# demo7.net
KiCad netlist of a schematic drawn in EAGLE
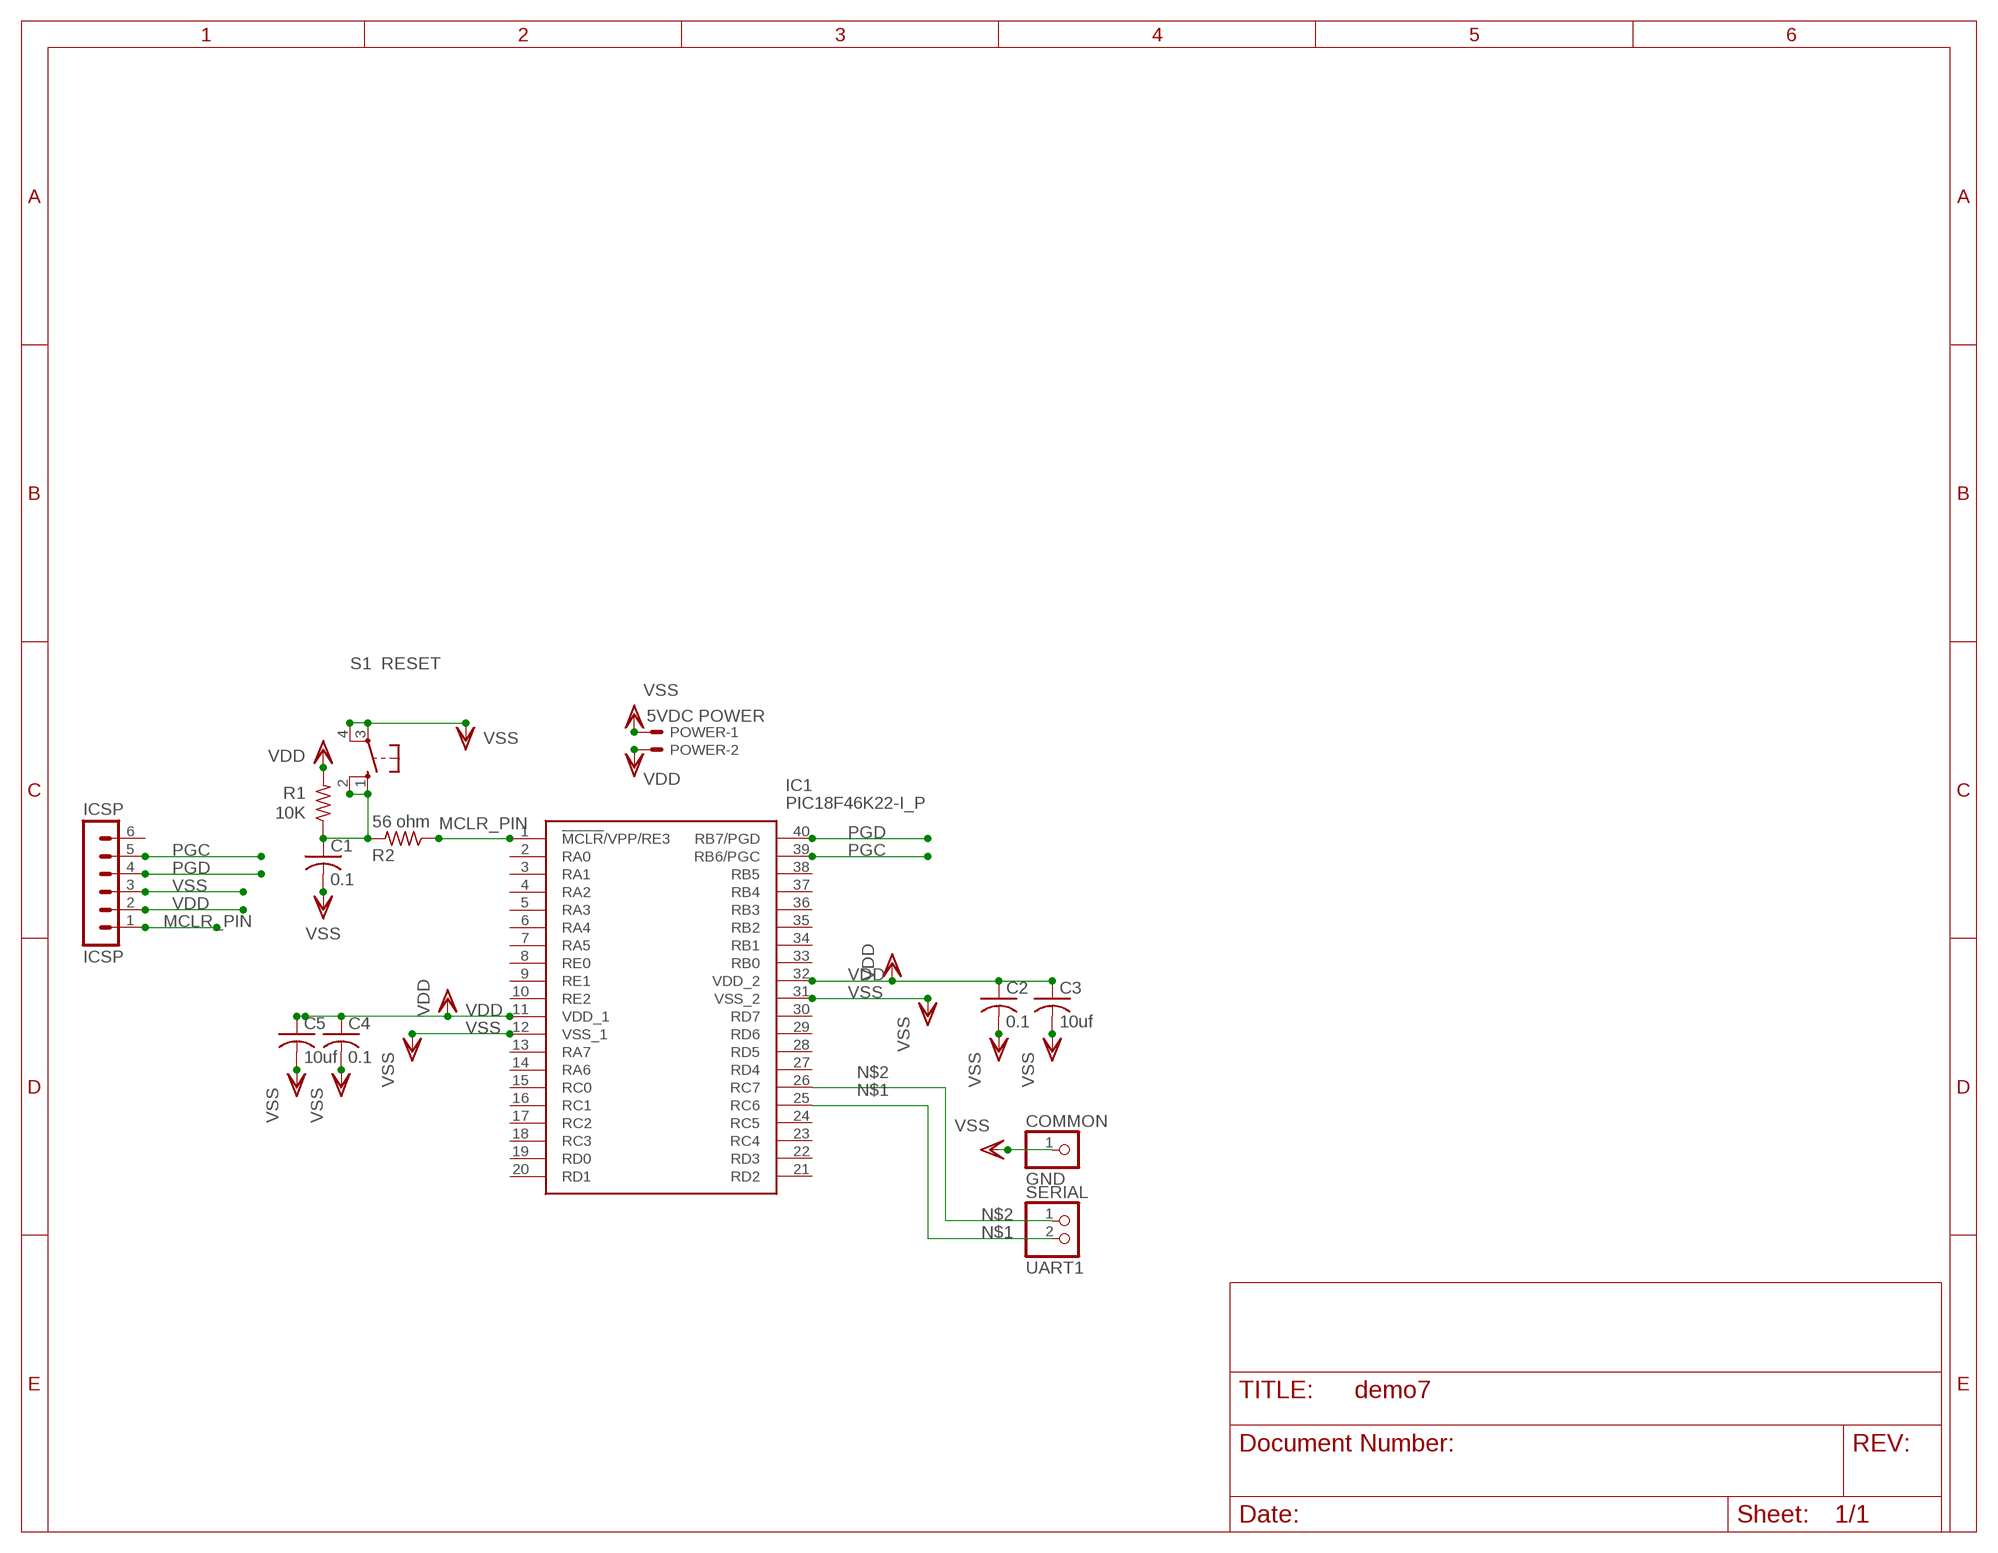
[diagram p0: schematic, sheet 1]

(export (version "E")
  (design (tool "Eeschema 10.0.6"))
  (components
    (comp (ref "C1")
      (value "0.1")
      (footprint "eagle-import:C025-030X050")
      (libsource (lib "eagle-import") (part "C-US025-030X050"))
    )
    (comp (ref "C2")
      (value "0.1")
      (footprint "eagle-import:C025-030X050")
      (libsource (lib "eagle-import") (part "C-US025-030X050"))
    )
    (comp (ref "C3")
      (value "10uf")
      (footprint "eagle-import:C025-030X050")
      (libsource (lib "eagle-import") (part "C-US025-030X050"))
    )
    (comp (ref "C4")
      (value "0.1")
      (footprint "eagle-import:C025-030X050")
      (libsource (lib "eagle-import") (part "C-US025-030X050"))
    )
    (comp (ref "C5")
      (value "10uf")
      (footprint "eagle-import:C025-030X050")
      (libsource (lib "eagle-import") (part "C-US025-030X050"))
    )
    (comp (ref "COMMON")
      (value "GND")
      (footprint "eagle-import:1X01")
      (libsource (lib "eagle-import") (part "PINHD-1X1"))
    )
    (comp (ref "IC1")
      (value "PIC18F46K22-I_P")
      (footprint "eagle-import:DIP1543W58P254L5175H635Q40N")
      (fields
        (field (name "MANUFACTURER_PART_NUMBER") "PIC18F46K22-I/P")
        (field (name "MOUSER_PART_NUMBER") "579-PIC18F46K22IP")
      )
      (libsource (lib "eagle-import") (part "PIC18F46K22-I_P"))
    )
    (comp (ref "ICSP")
      (value "ICSP")
      (footprint "eagle-import:MA06-1")
      (libsource (lib "eagle-import") (part "MA06-1"))
    )
    (comp (ref "POWER")
      (value "5VDC POWER")
      (footprint "eagle-import:22-23-2021")
      (fields (field (name "MF") "MOLEX") (field (name "MPN") "22-23-2021"))
      (libsource (lib "eagle-import") (part "22-23-2021"))
    )
    (comp (ref "R1")
      (value "10K")
      (footprint "eagle-import:0204_7")
      (libsource (lib "eagle-import") (part "R-US_0204/7"))
    )
    (comp (ref "R2")
      (value "56 ohm")
      (footprint "eagle-import:0204_7")
      (libsource (lib "eagle-import") (part "R-US_0204/7"))
    )
    (comp (ref "S1")
      (value "RESET")
      (footprint "eagle-import:B3F-10XX")
      (fields (field (name "MPN") "B3F-1000"))
      (libsource (lib "eagle-import") (part "10-XX"))
    )
    (comp (ref "SERIAL")
      (value "UART1")
      (footprint "eagle-import:1X02")
      (libsource (lib "eagle-import") (part "PINHD-1X2"))
    )
  )
  (nets
    (net (code "1") (name "/MCLR_PIN") (class "Default")
      (node (ref "IC1") (pin "1") (pinfunction "~{MCLR}/VPP/RE3_1") (pintype "bidirectional"))
      (node (ref "ICSP") (pin "1") (pinfunction "1_1") (pintype "passive"))
      (node (ref "R2") (pin "1") (pinfunction "1_1") (pintype "passive"))
    )
    (net (code "2") (name "/N$1") (class "Default")
      (node (ref "IC1") (pin "25") (pinfunction "RC6_25") (pintype "bidirectional"))
      (node (ref "SERIAL") (pin "2") (pinfunction "2_2") (pintype "passive"))
    )
    (net (code "3") (name "/N$2") (class "Default")
      (node (ref "IC1") (pin "26") (pinfunction "RC7_26") (pintype "bidirectional"))
      (node (ref "SERIAL") (pin "1") (pinfunction "1_1") (pintype "passive"))
    )
    (net (code "4") (name "/PGC") (class "Default")
      (node (ref "IC1") (pin "39") (pinfunction "RB6/PGC_39") (pintype "bidirectional"))
      (node (ref "ICSP") (pin "5") (pinfunction "5_5") (pintype "passive"))
    )
    (net (code "5") (name "/PGD") (class "Default")
      (node (ref "IC1") (pin "40") (pinfunction "RB7/PGD_40") (pintype "bidirectional"))
      (node (ref "ICSP") (pin "4") (pinfunction "4_4") (pintype "passive"))
    )
    (net (code "6") (name "Net-(S1-S)") (class "Default")
      (node (ref "C1") (pin "1") (pinfunction "1_1") (pintype "passive"))
      (node (ref "R1") (pin "1") (pinfunction "1_1") (pintype "passive"))
      (node (ref "R2") (pin "2") (pinfunction "2_2") (pintype "passive"))
      (node (ref "S1") (pin "1") (pinfunction "S_1") (pintype "passive"))
      (node (ref "S1") (pin "2") (pinfunction "S1_2") (pintype "passive"))
    )
    (net (code "7") (name "VDD") (class "Default")
      (node (ref "C2") (pin "1") (pinfunction "1_1") (pintype "passive"))
      (node (ref "C3") (pin "1") (pinfunction "1_1") (pintype "passive"))
      (node (ref "C4") (pin "1") (pinfunction "1_1") (pintype "passive"))
      (node (ref "C5") (pin "1") (pinfunction "1_1") (pintype "passive"))
      (node (ref "IC1") (pin "11") (pinfunction "VDD_1_11") (pintype "bidirectional"))
      (node (ref "IC1") (pin "32") (pinfunction "VDD_2_32") (pintype "bidirectional"))
      (node (ref "ICSP") (pin "2") (pinfunction "2_2") (pintype "passive"))
      (node (ref "POWER") (pin "2") (pinfunction "S_2") (pintype "passive"))
      (node (ref "R1") (pin "2") (pinfunction "2_2") (pintype "passive"))
    )
    (net (code "8") (name "VSS") (class "Default")
      (node (ref "C1") (pin "2") (pinfunction "2_2") (pintype "passive"))
      (node (ref "C2") (pin "2") (pinfunction "2_2") (pintype "passive"))
      (node (ref "C3") (pin "2") (pinfunction "2_2") (pintype "passive"))
      (node (ref "C4") (pin "2") (pinfunction "2_2") (pintype "passive"))
      (node (ref "C5") (pin "2") (pinfunction "2_2") (pintype "passive"))
      (node (ref "COMMON") (pin "1") (pinfunction "1_1") (pintype "passive"))
      (node (ref "IC1") (pin "12") (pinfunction "VSS_1_12") (pintype "bidirectional"))
      (node (ref "IC1") (pin "31") (pinfunction "VSS_2_31") (pintype "bidirectional"))
      (node (ref "ICSP") (pin "3") (pinfunction "3_3") (pintype "passive"))
      (node (ref "POWER") (pin "1") (pinfunction "S_1") (pintype "passive"))
      (node (ref "S1") (pin "3") (pinfunction "P_3") (pintype "passive"))
      (node (ref "S1") (pin "4") (pinfunction "P1_4") (pintype "passive"))
    )
    (net (code "9") (name "unconnected-(IC1-RA0-Pad2)") (class "Default")
      (node (ref "IC1") (pin "2") (pinfunction "RA0_2") (pintype "bidirectional"))
    )
    (net (code "10") (name "unconnected-(IC1-RA1-Pad3)") (class "Default")
      (node (ref "IC1") (pin "3") (pinfunction "RA1_3") (pintype "bidirectional"))
    )
    (net (code "11") (name "unconnected-(IC1-RA2-Pad4)") (class "Default")
      (node (ref "IC1") (pin "4") (pinfunction "RA2_4") (pintype "bidirectional"))
    )
    (net (code "12") (name "unconnected-(IC1-RA3-Pad5)") (class "Default")
      (node (ref "IC1") (pin "5") (pinfunction "RA3_5") (pintype "bidirectional"))
    )
    (net (code "13") (name "unconnected-(IC1-RA4-Pad6)") (class "Default")
      (node (ref "IC1") (pin "6") (pinfunction "RA4_6") (pintype "bidirectional"))
    )
    (net (code "14") (name "unconnected-(IC1-RA5-Pad7)") (class "Default")
      (node (ref "IC1") (pin "7") (pinfunction "RA5_7") (pintype "bidirectional"))
    )
    (net (code "15") (name "unconnected-(IC1-RA6-Pad14)") (class "Default")
      (node (ref "IC1") (pin "14") (pinfunction "RA6_14") (pintype "bidirectional"))
    )
    (net (code "16") (name "unconnected-(IC1-RA7-Pad13)") (class "Default")
      (node (ref "IC1") (pin "13") (pinfunction "RA7_13") (pintype "bidirectional"))
    )
    (net (code "17") (name "unconnected-(IC1-RB0-Pad33)") (class "Default")
      (node (ref "IC1") (pin "33") (pinfunction "RB0_33") (pintype "bidirectional"))
    )
    (net (code "18") (name "unconnected-(IC1-RB1-Pad34)") (class "Default")
      (node (ref "IC1") (pin "34") (pinfunction "RB1_34") (pintype "bidirectional"))
    )
    (net (code "19") (name "unconnected-(IC1-RB2-Pad35)") (class "Default")
      (node (ref "IC1") (pin "35") (pinfunction "RB2_35") (pintype "bidirectional"))
    )
    (net (code "20") (name "unconnected-(IC1-RB3-Pad36)") (class "Default")
      (node (ref "IC1") (pin "36") (pinfunction "RB3_36") (pintype "bidirectional"))
    )
    (net (code "21") (name "unconnected-(IC1-RB4-Pad37)") (class "Default")
      (node (ref "IC1") (pin "37") (pinfunction "RB4_37") (pintype "bidirectional"))
    )
    (net (code "22") (name "unconnected-(IC1-RB5-Pad38)") (class "Default")
      (node (ref "IC1") (pin "38") (pinfunction "RB5_38") (pintype "bidirectional"))
    )
    (net (code "23") (name "unconnected-(IC1-RC0-Pad15)") (class "Default")
      (node (ref "IC1") (pin "15") (pinfunction "RC0_15") (pintype "bidirectional"))
    )
    (net (code "24") (name "unconnected-(IC1-RC1-Pad16)") (class "Default")
      (node (ref "IC1") (pin "16") (pinfunction "RC1_16") (pintype "bidirectional"))
    )
    (net (code "25") (name "unconnected-(IC1-RC2-Pad17)") (class "Default")
      (node (ref "IC1") (pin "17") (pinfunction "RC2_17") (pintype "bidirectional"))
    )
    (net (code "26") (name "unconnected-(IC1-RC3-Pad18)") (class "Default")
      (node (ref "IC1") (pin "18") (pinfunction "RC3_18") (pintype "bidirectional"))
    )
    (net (code "27") (name "unconnected-(IC1-RC4-Pad23)") (class "Default")
      (node (ref "IC1") (pin "23") (pinfunction "RC4_23") (pintype "bidirectional"))
    )
    (net (code "28") (name "unconnected-(IC1-RC5-Pad24)") (class "Default")
      (node (ref "IC1") (pin "24") (pinfunction "RC5_24") (pintype "bidirectional"))
    )
    (net (code "29") (name "unconnected-(IC1-RD0-Pad19)") (class "Default")
      (node (ref "IC1") (pin "19") (pinfunction "RD0_19") (pintype "bidirectional"))
    )
    (net (code "30") (name "unconnected-(IC1-RD1-Pad20)") (class "Default")
      (node (ref "IC1") (pin "20") (pinfunction "RD1_20") (pintype "bidirectional"))
    )
    (net (code "31") (name "unconnected-(IC1-RD2-Pad21)") (class "Default")
      (node (ref "IC1") (pin "21") (pinfunction "RD2_21") (pintype "bidirectional"))
    )
    (net (code "32") (name "unconnected-(IC1-RD3-Pad22)") (class "Default")
      (node (ref "IC1") (pin "22") (pinfunction "RD3_22") (pintype "bidirectional"))
    )
    (net (code "33") (name "unconnected-(IC1-RD4-Pad27)") (class "Default")
      (node (ref "IC1") (pin "27") (pinfunction "RD4_27") (pintype "bidirectional"))
    )
    (net (code "34") (name "unconnected-(IC1-RD5-Pad28)") (class "Default")
      (node (ref "IC1") (pin "28") (pinfunction "RD5_28") (pintype "bidirectional"))
    )
    (net (code "35") (name "unconnected-(IC1-RD6-Pad29)") (class "Default")
      (node (ref "IC1") (pin "29") (pinfunction "RD6_29") (pintype "bidirectional"))
    )
    (net (code "36") (name "unconnected-(IC1-RD7-Pad30)") (class "Default")
      (node (ref "IC1") (pin "30") (pinfunction "RD7_30") (pintype "bidirectional"))
    )
    (net (code "37") (name "unconnected-(IC1-RE0-Pad8)") (class "Default")
      (node (ref "IC1") (pin "8") (pinfunction "RE0_8") (pintype "bidirectional"))
    )
    (net (code "38") (name "unconnected-(IC1-RE1-Pad9)") (class "Default")
      (node (ref "IC1") (pin "9") (pinfunction "RE1_9") (pintype "bidirectional"))
    )
    (net (code "39") (name "unconnected-(IC1-RE2-Pad10)") (class "Default")
      (node (ref "IC1") (pin "10") (pinfunction "RE2_10") (pintype "bidirectional"))
    )
    (net (code "40") (name "unconnected-(ICSP-Pad6)") (class "Default")
      (node (ref "ICSP") (pin "6") (pinfunction "6_6") (pintype "passive"))
    )
  )
)
